# Top.net
KiCad netlist of a schematic drawn in Altium Designer
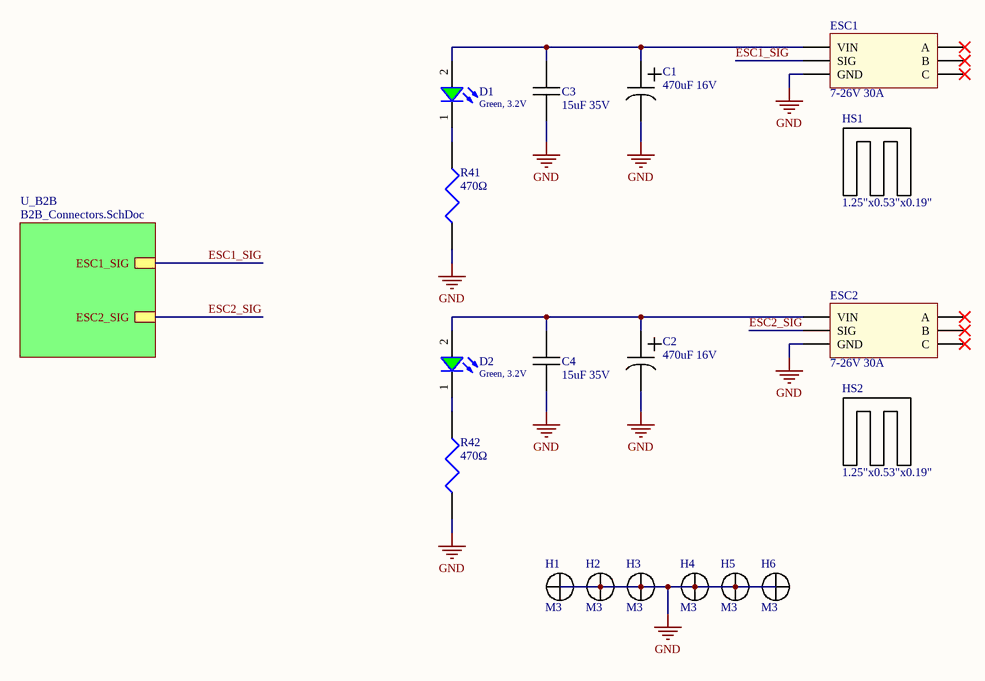
[diagram p0: Top.SchDoc]

(export (version "E")
  (design (tool "Eeschema 10.0.6"))
  (components
    (comp (ref "C1")
      (value "470uF 16V")
      (footprint "875115357006")
      (description "Wurth CAP ALUM POLY 470UF 20% 16V SMD")
      (fields (field (name "PART NUMBER") "875115357006") (field (name "MANUFACTURER") "Würth Elektronik"))
      (libsource (lib "MinesROV") (part "875115357006"))
    )
    (comp (ref "C2")
      (value "470uF 16V")
      (footprint "875115357006")
      (description "Wurth CAP ALUM POLY 470UF 20% 16V SMD")
      (fields (field (name "PART NUMBER") "875115357006") (field (name "MANUFACTURER") "Würth Elektronik"))
      (libsource (lib "MinesROV") (part "875115357006"))
    )
    (comp (ref "C3")
      (value "15uF 35V")
      (footprint "C2012M Generic")
      (description "TDK CAP CER 15UF 35V X5R 0805")
      (fields
        (field (name "PART NUMBER") "C2012X5R1V156M125AC")
        (field (name "MANUFACTURER") "TDK Corporation")
      )
      (libsource (lib "MinesROV") (part "C2012X5R1V156M125AC"))
    )
    (comp (ref "C4")
      (value "15uF 35V")
      (footprint "C2012M Generic")
      (description "TDK CAP CER 15UF 35V X5R 0805")
      (fields
        (field (name "PART NUMBER") "C2012X5R1V156M125AC")
        (field (name "MANUFACTURER") "TDK Corporation")
      )
      (libsource (lib "MinesROV") (part "C2012X5R1V156M125AC"))
    )
    (comp (ref "D1")
      (value "Green, 3.2V")
      (footprint "WL-SMCW_1206")
      (description "WL-SMCW SMT Mono-color Chip LED Waterclear, size 1206, Green, 3.2V, 140deg")
      (fields (field (name "PART NUMBER") "150120GS75000") (field (name "PUBLISHER") "Wurth Elektronik"))
      (libsource (lib "MinesROV") (part "150120GS75000"))
    )
    (comp (ref "D2")
      (value "Green, 3.2V")
      (footprint "WL-SMCW_1206")
      (description "WL-SMCW SMT Mono-color Chip LED Waterclear, size 1206, Green, 3.2V, 140deg")
      (fields (field (name "PART NUMBER") "150120GS75000") (field (name "PUBLISHER") "Wurth Elektronik"))
      (libsource (lib "MinesROV") (part "150120GS75000"))
    )
    (comp (ref "ESC1")
      (value "7-26V 30A")
      (footprint "BasicESC")
      (description "Blue Robotics BasicESC")
      (fields (field (name "MANUFACTURER") "Blue Robotics"))
      (libsource (lib "MinesROV") (part "BasicESC"))
    )
    (comp (ref "ESC2")
      (value "7-26V 30A")
      (footprint "BasicESC")
      (description "Blue Robotics BasicESC")
      (fields (field (name "MANUFACTURER") "Blue Robotics"))
      (libsource (lib "MinesROV") (part "BasicESC"))
    )
    (comp (ref "H1")
      (value "M3")
      (footprint "M3_MOUNTING_HOLE")
      (description "MECHANICAL M3 Mounting Hole")
      (libsource (lib "MinesROV") (part "M3_Mounting_Hole"))
    )
    (comp (ref "H2")
      (value "M3")
      (footprint "M3_MOUNTING_HOLE")
      (description "MECHANICAL M3 Mounting Hole")
      (libsource (lib "MinesROV") (part "M3_Mounting_Hole"))
    )
    (comp (ref "H3")
      (value "M3")
      (footprint "M3_MOUNTING_HOLE")
      (description "MECHANICAL M3 Mounting Hole")
      (libsource (lib "MinesROV") (part "M3_Mounting_Hole"))
    )
    (comp (ref "H4")
      (value "M3")
      (footprint "M3_MOUNTING_HOLE")
      (description "MECHANICAL M3 Mounting Hole")
      (libsource (lib "MinesROV") (part "M3_Mounting_Hole"))
    )
    (comp (ref "H5")
      (value "M3")
      (footprint "M3_MOUNTING_HOLE")
      (description "MECHANICAL M3 Mounting Hole")
      (libsource (lib "MinesROV") (part "M3_Mounting_Hole"))
    )
    (comp (ref "H6")
      (value "M3")
      (footprint "M3_MOUNTING_HOLE")
      (description "MECHANICAL M3 Mounting Hole")
      (libsource (lib "MinesROV") (part "M3_Mounting_Hole"))
    )
    (comp (ref "HS1")
      (value "1.25\"x0.53\"x0.19\"")
      (footprint "508500B00000G")
      (description "AAVID HEATSINK 24-PIN DIP GLUE-ON BLK")
      (fields
        (field (name "MANUFACTURER") "Aavid, Thermal Division of Boyd Corporation")
        (field (name "PART NUMBER") "508500B00000G")
      )
      (libsource (lib "MinesROV") (part "508500B00000G"))
    )
    (comp (ref "HS2")
      (value "1.25\"x0.53\"x0.19\"")
      (footprint "508500B00000G")
      (description "AAVID HEATSINK 24-PIN DIP GLUE-ON BLK")
      (fields
        (field (name "MANUFACTURER") "Aavid, Thermal Division of Boyd Corporation")
        (field (name "PART NUMBER") "508500B00000G")
      )
      (libsource (lib "MinesROV") (part "508500B00000G"))
    )
    (comp (ref "R41")
      (value "470Ω")
      (footprint "RMCF1206")
      (description "Stackpole RES 470 OHM 5% 1/4W 1206")
      (fields
        (field (name "PART NUMBER") "RMCF1206JT470R")
        (field (name "MANUFACTURER") "Stackpole Electronics Inc")
      )
      (libsource (lib "MinesROV") (part "RMCF1206JT470R"))
    )
    (comp (ref "R42")
      (value "470Ω")
      (footprint "RMCF1206")
      (description "Stackpole RES 470 OHM 5% 1/4W 1206")
      (fields
        (field (name "PART NUMBER") "RMCF1206JT470R")
        (field (name "MANUFACTURER") "Stackpole Electronics Inc")
      )
      (libsource (lib "MinesROV") (part "RMCF1206JT470R"))
    )
  )
  (nets
    (net (code "1") (name "/ESC1_SIG") (class "Default")
      (node (ref "ESC1") (pin "SIG") (pinfunction "SIG_SIG") (pintype "passive"))
    )
    (net (code "2") (name "/ESC2_SIG") (class "Default")
      (node (ref "ESC2") (pin "SIG") (pinfunction "SIG_SIG") (pintype "passive"))
    )
    (net (code "3") (name "GND") (class "Default")
      (node (ref "C1") (pin "2") (pinfunction "2_2") (pintype "passive"))
      (node (ref "C2") (pin "2") (pinfunction "2_2") (pintype "passive"))
      (node (ref "C3") (pin "2") (pinfunction "2_2") (pintype "passive"))
      (node (ref "C4") (pin "2") (pinfunction "2_2") (pintype "passive"))
      (node (ref "ESC1") (pin "GND") (pinfunction "GND_GND") (pintype "passive"))
      (node (ref "ESC2") (pin "GND") (pinfunction "GND_GND") (pintype "passive"))
      (node (ref "H1") (pin "1") (pinfunction "1_1") (pintype "passive"))
      (node (ref "H2") (pin "1") (pinfunction "1_1") (pintype "passive"))
      (node (ref "H3") (pin "1") (pinfunction "1_1") (pintype "passive"))
      (node (ref "H4") (pin "1") (pinfunction "1_1") (pintype "passive"))
      (node (ref "H5") (pin "1") (pinfunction "1_1") (pintype "passive"))
      (node (ref "H6") (pin "1") (pinfunction "1_1") (pintype "passive"))
      (node (ref "R41") (pin "1") (pinfunction "1_1") (pintype "passive"))
      (node (ref "R42") (pin "1") (pinfunction "1_1") (pintype "passive"))
    )
    (net (code "4") (name "Net-(D1-A)") (class "Default")
      (node (ref "C1") (pin "1") (pinfunction "1_1") (pintype "passive"))
      (node (ref "C3") (pin "1") (pinfunction "1_1") (pintype "passive"))
      (node (ref "D1") (pin "2") (pinfunction "A_2") (pintype "passive"))
      (node (ref "ESC1") (pin "VIN") (pinfunction "VIN_VIN") (pintype "passive"))
    )
    (net (code "5") (name "Net-(D1-K)") (class "Default")
      (node (ref "D1") (pin "1") (pinfunction "K_1") (pintype "passive"))
      (node (ref "R41") (pin "2") (pinfunction "2_2") (pintype "passive"))
    )
    (net (code "6") (name "Net-(D2-A)") (class "Default")
      (node (ref "C2") (pin "1") (pinfunction "1_1") (pintype "passive"))
      (node (ref "C4") (pin "1") (pinfunction "1_1") (pintype "passive"))
      (node (ref "D2") (pin "2") (pinfunction "A_2") (pintype "passive"))
      (node (ref "ESC2") (pin "VIN") (pinfunction "VIN_VIN") (pintype "passive"))
    )
    (net (code "7") (name "Net-(D2-K)") (class "Default")
      (node (ref "D2") (pin "1") (pinfunction "K_1") (pintype "passive"))
      (node (ref "R42") (pin "2") (pinfunction "2_2") (pintype "passive"))
    )
    (net (code "8") (name "unconnected-(ESC1-PadA)") (class "Default")
      (node (ref "ESC1") (pin "A") (pinfunction "A_A") (pintype "passive+no_connect"))
    )
    (net (code "9") (name "unconnected-(ESC1-PadB)") (class "Default")
      (node (ref "ESC1") (pin "B") (pinfunction "B_B") (pintype "passive+no_connect"))
    )
    (net (code "10") (name "unconnected-(ESC1-PadC)") (class "Default")
      (node (ref "ESC1") (pin "C") (pinfunction "C_C") (pintype "passive+no_connect"))
    )
    (net (code "11") (name "unconnected-(ESC2-PadA)") (class "Default")
      (node (ref "ESC2") (pin "A") (pinfunction "A_A") (pintype "passive+no_connect"))
    )
    (net (code "12") (name "unconnected-(ESC2-PadB)") (class "Default")
      (node (ref "ESC2") (pin "B") (pinfunction "B_B") (pintype "passive+no_connect"))
    )
    (net (code "13") (name "unconnected-(ESC2-PadC)") (class "Default")
      (node (ref "ESC2") (pin "C") (pinfunction "C_C") (pintype "passive+no_connect"))
    )
  )
)
